# Schematic.net
KiCad netlist of a schematic drawn in Altium Designer
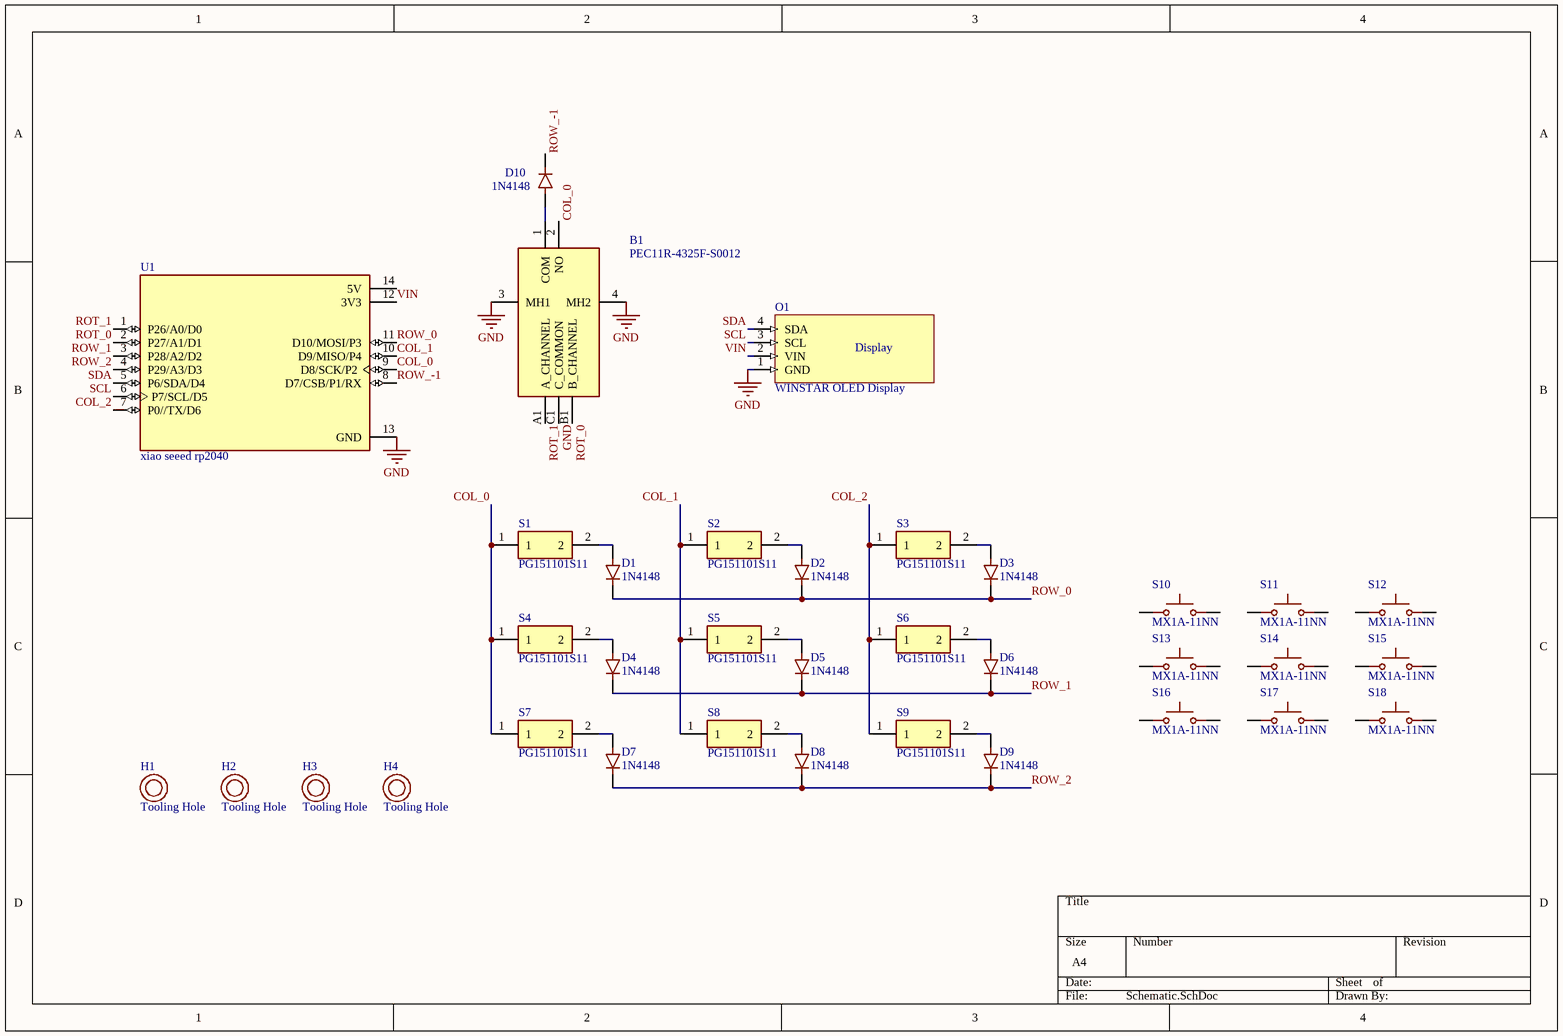
[diagram p0: Schematic.SchDoc]

(export (version "E")
  (design (tool "Eeschema 10.0.6"))
  (components
    (comp (ref "B1")
      (value "PEC11R-4325F-S0012")
      (footprint "PEC11R-4315F-S0012")
      (description "Rotary Encoder Mechanical 12 Quadrature (Incremental) Vertical")
      (fields (field (name "MOUSER PART NUMBER") "652-PEC11R4325FS0012"))
      (libsource (lib "Schematic_Lib") (part "PEC11R-4315F-S0012"))
    )
    (comp (ref "D1")
      (value "1N4148")
      (footprint "1N4148 Diode")
      (description "Diode Standard 75V 200mA Surface Mount SOD-523F")
      (fields (field (name "MF") "ON Semiconductor"))
      (libsource (lib "Schematic_Lib") (part "1N4148"))
    )
    (comp (ref "D2")
      (value "1N4148")
      (footprint "1N4148 Diode")
      (description "Diode Standard 75V 200mA Surface Mount SOD-523F")
      (fields (field (name "MF") "ON Semiconductor"))
      (libsource (lib "Schematic_Lib") (part "1N4148"))
    )
    (comp (ref "D3")
      (value "1N4148")
      (footprint "1N4148 Diode")
      (description "Diode Standard 75V 200mA Surface Mount SOD-523F")
      (fields (field (name "MF") "ON Semiconductor"))
      (libsource (lib "Schematic_Lib") (part "1N4148"))
    )
    (comp (ref "D4")
      (value "1N4148")
      (footprint "1N4148 Diode")
      (description "Diode Standard 75V 200mA Surface Mount SOD-523F")
      (fields (field (name "MF") "ON Semiconductor"))
      (libsource (lib "Schematic_Lib") (part "1N4148"))
    )
    (comp (ref "D5")
      (value "1N4148")
      (footprint "1N4148 Diode")
      (description "Diode Standard 75V 200mA Surface Mount SOD-523F")
      (fields (field (name "MF") "ON Semiconductor"))
      (libsource (lib "Schematic_Lib") (part "1N4148"))
    )
    (comp (ref "D6")
      (value "1N4148")
      (footprint "1N4148 Diode")
      (description "Diode Standard 75V 200mA Surface Mount SOD-523F")
      (fields (field (name "MF") "ON Semiconductor"))
      (libsource (lib "Schematic_Lib") (part "1N4148"))
    )
    (comp (ref "D7")
      (value "1N4148")
      (footprint "1N4148 Diode")
      (description "Diode Standard 75V 200mA Surface Mount SOD-523F")
      (fields (field (name "MF") "ON Semiconductor"))
      (libsource (lib "Schematic_Lib") (part "1N4148"))
    )
    (comp (ref "D8")
      (value "1N4148")
      (footprint "1N4148 Diode")
      (description "Diode Standard 75V 200mA Surface Mount SOD-523F")
      (fields (field (name "MF") "ON Semiconductor"))
      (libsource (lib "Schematic_Lib") (part "1N4148"))
    )
    (comp (ref "D9")
      (value "1N4148")
      (footprint "1N4148 Diode")
      (description "Diode Standard 75V 200mA Surface Mount SOD-523F")
      (fields (field (name "MF") "ON Semiconductor"))
      (libsource (lib "Schematic_Lib") (part "1N4148"))
    )
    (comp (ref "D10")
      (value "1N4148")
      (footprint "1N4148 Diode")
      (description "Diode Standard 75V 200mA Surface Mount SOD-523F")
      (fields (field (name "MF") "ON Semiconductor"))
      (libsource (lib "Schematic_Lib") (part "1N4148"))
    )
    (comp (ref "H1")
      (value "Tooling Hole")
      (footprint "Tooling Hole")
      (libsource (lib "Schematic_Lib") (part "Tooling Hole"))
    )
    (comp (ref "H2")
      (value "Tooling Hole")
      (footprint "Tooling Hole")
      (libsource (lib "Schematic_Lib") (part "Tooling Hole"))
    )
    (comp (ref "H3")
      (value "Tooling Hole")
      (footprint "Tooling Hole")
      (libsource (lib "Schematic_Lib") (part "Tooling Hole"))
    )
    (comp (ref "H4")
      (value "Tooling Hole")
      (footprint "Tooling Hole")
      (libsource (lib "Schematic_Lib") (part "Tooling Hole"))
    )
    (comp (ref "O1")
      (value "WINSTAR OLED Display")
      (footprint "WINSTAR OLED Display")
      (description "WEA012832FWPP3N00000")
      (libsource (lib "Schematic_Lib") (part "WINSTAR OLED Display"))
    )
    (comp (ref "S1")
      (value "PG151101S11")
      (footprint "SW_PG151101S11")
      (fields (field (name "MF") "Kailh"))
      (libsource (lib "Schematic_Lib") (part "PG151101S11"))
    )
    (comp (ref "S2")
      (value "PG151101S11")
      (footprint "SW_PG151101S11")
      (fields (field (name "MF") "Kailh"))
      (libsource (lib "Schematic_Lib") (part "PG151101S11"))
    )
    (comp (ref "S3")
      (value "PG151101S11")
      (footprint "SW_PG151101S11")
      (fields (field (name "MF") "Kailh"))
      (libsource (lib "Schematic_Lib") (part "PG151101S11"))
    )
    (comp (ref "S4")
      (value "PG151101S11")
      (footprint "SW_PG151101S11")
      (fields (field (name "MF") "Kailh"))
      (libsource (lib "Schematic_Lib") (part "PG151101S11"))
    )
    (comp (ref "S5")
      (value "PG151101S11")
      (footprint "SW_PG151101S11")
      (fields (field (name "MF") "Kailh"))
      (libsource (lib "Schematic_Lib") (part "PG151101S11"))
    )
    (comp (ref "S6")
      (value "PG151101S11")
      (footprint "SW_PG151101S11")
      (fields (field (name "MF") "Kailh"))
      (libsource (lib "Schematic_Lib") (part "PG151101S11"))
    )
    (comp (ref "S7")
      (value "PG151101S11")
      (footprint "SW_PG151101S11")
      (fields (field (name "MF") "Kailh"))
      (libsource (lib "Schematic_Lib") (part "PG151101S11"))
    )
    (comp (ref "S8")
      (value "PG151101S11")
      (footprint "SW_PG151101S11")
      (fields (field (name "MF") "Kailh"))
      (libsource (lib "Schematic_Lib") (part "PG151101S11"))
    )
    (comp (ref "S9")
      (value "PG151101S11")
      (footprint "SW_PG151101S11")
      (fields (field (name "MF") "Kailh"))
      (libsource (lib "Schematic_Lib") (part "PG151101S11"))
    )
    (comp (ref "S10")
      (value "MX1A-11NN")
      (footprint "SW_MX1A-11NN")
      (fields (field (name "MF") "Cherry"))
      (libsource (lib "Schematic_Lib") (part "MX1A-11NN"))
    )
    (comp (ref "S11")
      (value "MX1A-11NN")
      (footprint "SW_MX1A-11NN")
      (fields (field (name "MF") "Cherry"))
      (libsource (lib "Schematic_Lib") (part "MX1A-11NN"))
    )
    (comp (ref "S12")
      (value "MX1A-11NN")
      (footprint "SW_MX1A-11NN")
      (fields (field (name "MF") "Cherry"))
      (libsource (lib "Schematic_Lib") (part "MX1A-11NN"))
    )
    (comp (ref "S13")
      (value "MX1A-11NN")
      (footprint "SW_MX1A-11NN")
      (fields (field (name "MF") "Cherry"))
      (libsource (lib "Schematic_Lib") (part "MX1A-11NN"))
    )
    (comp (ref "S14")
      (value "MX1A-11NN")
      (footprint "SW_MX1A-11NN")
      (fields (field (name "MF") "Cherry"))
      (libsource (lib "Schematic_Lib") (part "MX1A-11NN"))
    )
    (comp (ref "S15")
      (value "MX1A-11NN")
      (footprint "SW_MX1A-11NN")
      (fields (field (name "MF") "Cherry"))
      (libsource (lib "Schematic_Lib") (part "MX1A-11NN"))
    )
    (comp (ref "S16")
      (value "MX1A-11NN")
      (footprint "SW_MX1A-11NN")
      (fields (field (name "MF") "Cherry"))
      (libsource (lib "Schematic_Lib") (part "MX1A-11NN"))
    )
    (comp (ref "S17")
      (value "MX1A-11NN")
      (footprint "SW_MX1A-11NN")
      (fields (field (name "MF") "Cherry"))
      (libsource (lib "Schematic_Lib") (part "MX1A-11NN"))
    )
    (comp (ref "S18")
      (value "MX1A-11NN")
      (footprint "SW_MX1A-11NN")
      (fields (field (name "MF") "Cherry"))
      (libsource (lib "Schematic_Lib") (part "MX1A-11NN"))
    )
    (comp (ref "U1")
      (value "xiao seeed rp2040")
      (footprint "MODULE_102010428")
      (description "RP2040 XIAO RP2040 series ARMÂ® CortexÂ®-M0+ MCU 32-Bit Embedded Evaluation Board")
      (fields (field (name "MF") "Seeed Technology Co., Ltd") (field (name "MP") "102010428"))
      (libsource (lib "Schematic_Lib") (part "xiao seeed rp2040"))
    )
  )
  (nets
    (net (code "1") (name "/COL_0") (class "Default")
      (node (ref "B1") (pin "2") (pinfunction "NO_2") (pintype "passive"))
      (node (ref "S1") (pin "1") (pinfunction "1_1") (pintype "passive"))
      (node (ref "S4") (pin "1") (pinfunction "1_1") (pintype "passive"))
      (node (ref "S7") (pin "1") (pinfunction "1_1") (pintype "passive"))
      (node (ref "U1") (pin "9") (pinfunction "D8/SCK/P2_9") (pintype "bidirectional"))
    )
    (net (code "2") (name "/COL_1") (class "Default")
      (node (ref "S2") (pin "1") (pinfunction "1_1") (pintype "passive"))
      (node (ref "S5") (pin "1") (pinfunction "1_1") (pintype "passive"))
      (node (ref "S8") (pin "1") (pinfunction "1_1") (pintype "passive"))
      (node (ref "U1") (pin "10") (pinfunction "D9/MISO/P4_10") (pintype "bidirectional"))
    )
    (net (code "3") (name "/COL_2") (class "Default")
      (node (ref "S3") (pin "1") (pinfunction "1_1") (pintype "passive"))
      (node (ref "S6") (pin "1") (pinfunction "1_1") (pintype "passive"))
      (node (ref "S9") (pin "1") (pinfunction "1_1") (pintype "passive"))
      (node (ref "U1") (pin "7") (pinfunction "P0//TX/D6_7") (pintype "bidirectional"))
    )
    (net (code "4") (name "/ROT_0") (class "Default")
      (node (ref "B1") (pin "B1") (pinfunction "B_CHANNEL_B1") (pintype "passive"))
      (node (ref "U1") (pin "2") (pinfunction "P27/A1/D1_2") (pintype "bidirectional"))
    )
    (net (code "5") (name "/ROT_1") (class "Default")
      (node (ref "B1") (pin "A1") (pinfunction "A_CHANNEL_A1") (pintype "passive"))
      (node (ref "U1") (pin "1") (pinfunction "P26/A0/D0_1") (pintype "bidirectional"))
    )
    (net (code "6") (name "/ROW_-1") (class "Default")
      (node (ref "D10") (pin "K") (pinfunction "K_K") (pintype "passive"))
      (node (ref "U1") (pin "8") (pinfunction "D7/CSB/P1/RX_8") (pintype "bidirectional"))
    )
    (net (code "7") (name "/ROW_0") (class "Default")
      (node (ref "D1") (pin "K") (pinfunction "K_K") (pintype "passive"))
      (node (ref "D2") (pin "K") (pinfunction "K_K") (pintype "passive"))
      (node (ref "D3") (pin "K") (pinfunction "K_K") (pintype "passive"))
      (node (ref "U1") (pin "11") (pinfunction "D10/MOSI/P3_11") (pintype "bidirectional"))
    )
    (net (code "8") (name "/ROW_1") (class "Default")
      (node (ref "D4") (pin "K") (pinfunction "K_K") (pintype "passive"))
      (node (ref "D5") (pin "K") (pinfunction "K_K") (pintype "passive"))
      (node (ref "D6") (pin "K") (pinfunction "K_K") (pintype "passive"))
      (node (ref "U1") (pin "3") (pinfunction "P28/A2/D2_3") (pintype "bidirectional"))
    )
    (net (code "9") (name "/ROW_2") (class "Default")
      (node (ref "D7") (pin "K") (pinfunction "K_K") (pintype "passive"))
      (node (ref "D8") (pin "K") (pinfunction "K_K") (pintype "passive"))
      (node (ref "D9") (pin "K") (pinfunction "K_K") (pintype "passive"))
      (node (ref "U1") (pin "4") (pinfunction "P29/A3/D3_4") (pintype "bidirectional"))
    )
    (net (code "10") (name "/SCL") (class "Default")
      (node (ref "O1") (pin "3") (pinfunction "SCL_3") (pintype "input"))
      (node (ref "U1") (pin "6") (pinfunction "P7/SCL/D5_6") (pintype "bidirectional"))
    )
    (net (code "11") (name "/SDA") (class "Default")
      (node (ref "O1") (pin "4") (pinfunction "SDA_4") (pintype "input"))
      (node (ref "U1") (pin "5") (pinfunction "P6/SDA/D4_5") (pintype "bidirectional"))
    )
    (net (code "12") (name "/VIN") (class "Default")
      (node (ref "O1") (pin "2") (pinfunction "VIN_2") (pintype "input"))
      (node (ref "U1") (pin "12") (pinfunction "3V3_12") (pintype "power_in"))
    )
    (net (code "13") (name "GND") (class "Default")
      (node (ref "B1") (pin "3") (pinfunction "MH1_3") (pintype "passive"))
      (node (ref "B1") (pin "4") (pinfunction "MH2_4") (pintype "passive"))
      (node (ref "B1") (pin "C1") (pinfunction "C_COMMON_C1") (pintype "passive"))
      (node (ref "O1") (pin "1") (pinfunction "GND_1") (pintype "input"))
      (node (ref "U1") (pin "13") (pinfunction "GND_13") (pintype "power_in"))
    )
    (net (code "14") (name "Net-(B1-COM)") (class "Default")
      (node (ref "B1") (pin "1") (pinfunction "COM_1") (pintype "passive"))
      (node (ref "D10") (pin "A") (pinfunction "A_A") (pintype "passive"))
    )
    (net (code "15") (name "Net-(D1-PadA)") (class "Default")
      (node (ref "D1") (pin "A") (pinfunction "A_A") (pintype "passive"))
      (node (ref "S1") (pin "2") (pinfunction "2_2") (pintype "passive"))
    )
    (net (code "16") (name "Net-(D2-PadA)") (class "Default")
      (node (ref "D2") (pin "A") (pinfunction "A_A") (pintype "passive"))
      (node (ref "S2") (pin "2") (pinfunction "2_2") (pintype "passive"))
    )
    (net (code "17") (name "Net-(D3-PadA)") (class "Default")
      (node (ref "D3") (pin "A") (pinfunction "A_A") (pintype "passive"))
      (node (ref "S3") (pin "2") (pinfunction "2_2") (pintype "passive"))
    )
    (net (code "18") (name "Net-(D4-PadA)") (class "Default")
      (node (ref "D4") (pin "A") (pinfunction "A_A") (pintype "passive"))
      (node (ref "S4") (pin "2") (pinfunction "2_2") (pintype "passive"))
    )
    (net (code "19") (name "Net-(D5-PadA)") (class "Default")
      (node (ref "D5") (pin "A") (pinfunction "A_A") (pintype "passive"))
      (node (ref "S5") (pin "2") (pinfunction "2_2") (pintype "passive"))
    )
    (net (code "20") (name "Net-(D6-PadA)") (class "Default")
      (node (ref "D6") (pin "A") (pinfunction "A_A") (pintype "passive"))
      (node (ref "S6") (pin "2") (pinfunction "2_2") (pintype "passive"))
    )
    (net (code "21") (name "Net-(D7-PadA)") (class "Default")
      (node (ref "D7") (pin "A") (pinfunction "A_A") (pintype "passive"))
      (node (ref "S7") (pin "2") (pinfunction "2_2") (pintype "passive"))
    )
    (net (code "22") (name "Net-(D8-PadA)") (class "Default")
      (node (ref "D8") (pin "A") (pinfunction "A_A") (pintype "passive"))
      (node (ref "S8") (pin "2") (pinfunction "2_2") (pintype "passive"))
    )
    (net (code "23") (name "Net-(D9-PadA)") (class "Default")
      (node (ref "D9") (pin "A") (pinfunction "A_A") (pintype "passive"))
      (node (ref "S9") (pin "2") (pinfunction "2_2") (pintype "passive"))
    )
    (net (code "24") (name "unconnected-(S10-Pad1)") (class "Default")
      (node (ref "S10") (pin "1") (pinfunction "1_1") (pintype "passive"))
    )
    (net (code "25") (name "unconnected-(S10-Pad2)") (class "Default")
      (node (ref "S10") (pin "2") (pinfunction "2_2") (pintype "passive"))
    )
    (net (code "26") (name "unconnected-(S11-Pad1)") (class "Default")
      (node (ref "S11") (pin "1") (pinfunction "1_1") (pintype "passive"))
    )
    (net (code "27") (name "unconnected-(S11-Pad2)") (class "Default")
      (node (ref "S11") (pin "2") (pinfunction "2_2") (pintype "passive"))
    )
    (net (code "28") (name "unconnected-(S12-Pad1)") (class "Default")
      (node (ref "S12") (pin "1") (pinfunction "1_1") (pintype "passive"))
    )
    (net (code "29") (name "unconnected-(S12-Pad2)") (class "Default")
      (node (ref "S12") (pin "2") (pinfunction "2_2") (pintype "passive"))
    )
    (net (code "30") (name "unconnected-(S13-Pad1)") (class "Default")
      (node (ref "S13") (pin "1") (pinfunction "1_1") (pintype "passive"))
    )
    (net (code "31") (name "unconnected-(S13-Pad2)") (class "Default")
      (node (ref "S13") (pin "2") (pinfunction "2_2") (pintype "passive"))
    )
    (net (code "32") (name "unconnected-(S14-Pad1)") (class "Default")
      (node (ref "S14") (pin "1") (pinfunction "1_1") (pintype "passive"))
    )
    (net (code "33") (name "unconnected-(S14-Pad2)") (class "Default")
      (node (ref "S14") (pin "2") (pinfunction "2_2") (pintype "passive"))
    )
    (net (code "34") (name "unconnected-(S15-Pad1)") (class "Default")
      (node (ref "S15") (pin "1") (pinfunction "1_1") (pintype "passive"))
    )
    (net (code "35") (name "unconnected-(S15-Pad2)") (class "Default")
      (node (ref "S15") (pin "2") (pinfunction "2_2") (pintype "passive"))
    )
    (net (code "36") (name "unconnected-(S16-Pad1)") (class "Default")
      (node (ref "S16") (pin "1") (pinfunction "1_1") (pintype "passive"))
    )
    (net (code "37") (name "unconnected-(S16-Pad2)") (class "Default")
      (node (ref "S16") (pin "2") (pinfunction "2_2") (pintype "passive"))
    )
    (net (code "38") (name "unconnected-(S17-Pad1)") (class "Default")
      (node (ref "S17") (pin "1") (pinfunction "1_1") (pintype "passive"))
    )
    (net (code "39") (name "unconnected-(S17-Pad2)") (class "Default")
      (node (ref "S17") (pin "2") (pinfunction "2_2") (pintype "passive"))
    )
    (net (code "40") (name "unconnected-(S18-Pad1)") (class "Default")
      (node (ref "S18") (pin "1") (pinfunction "1_1") (pintype "passive"))
    )
    (net (code "41") (name "unconnected-(S18-Pad2)") (class "Default")
      (node (ref "S18") (pin "2") (pinfunction "2_2") (pintype "passive"))
    )
    (net (code "42") (name "unconnected-(U1-5V-Pad14)") (class "Default")
      (node (ref "U1") (pin "14") (pinfunction "5V_14") (pintype "power_in"))
    )
  )
)
